# SCH_shield_test_2024-01-07.net
KiCad netlist of a schematic drawn in EasyEDA
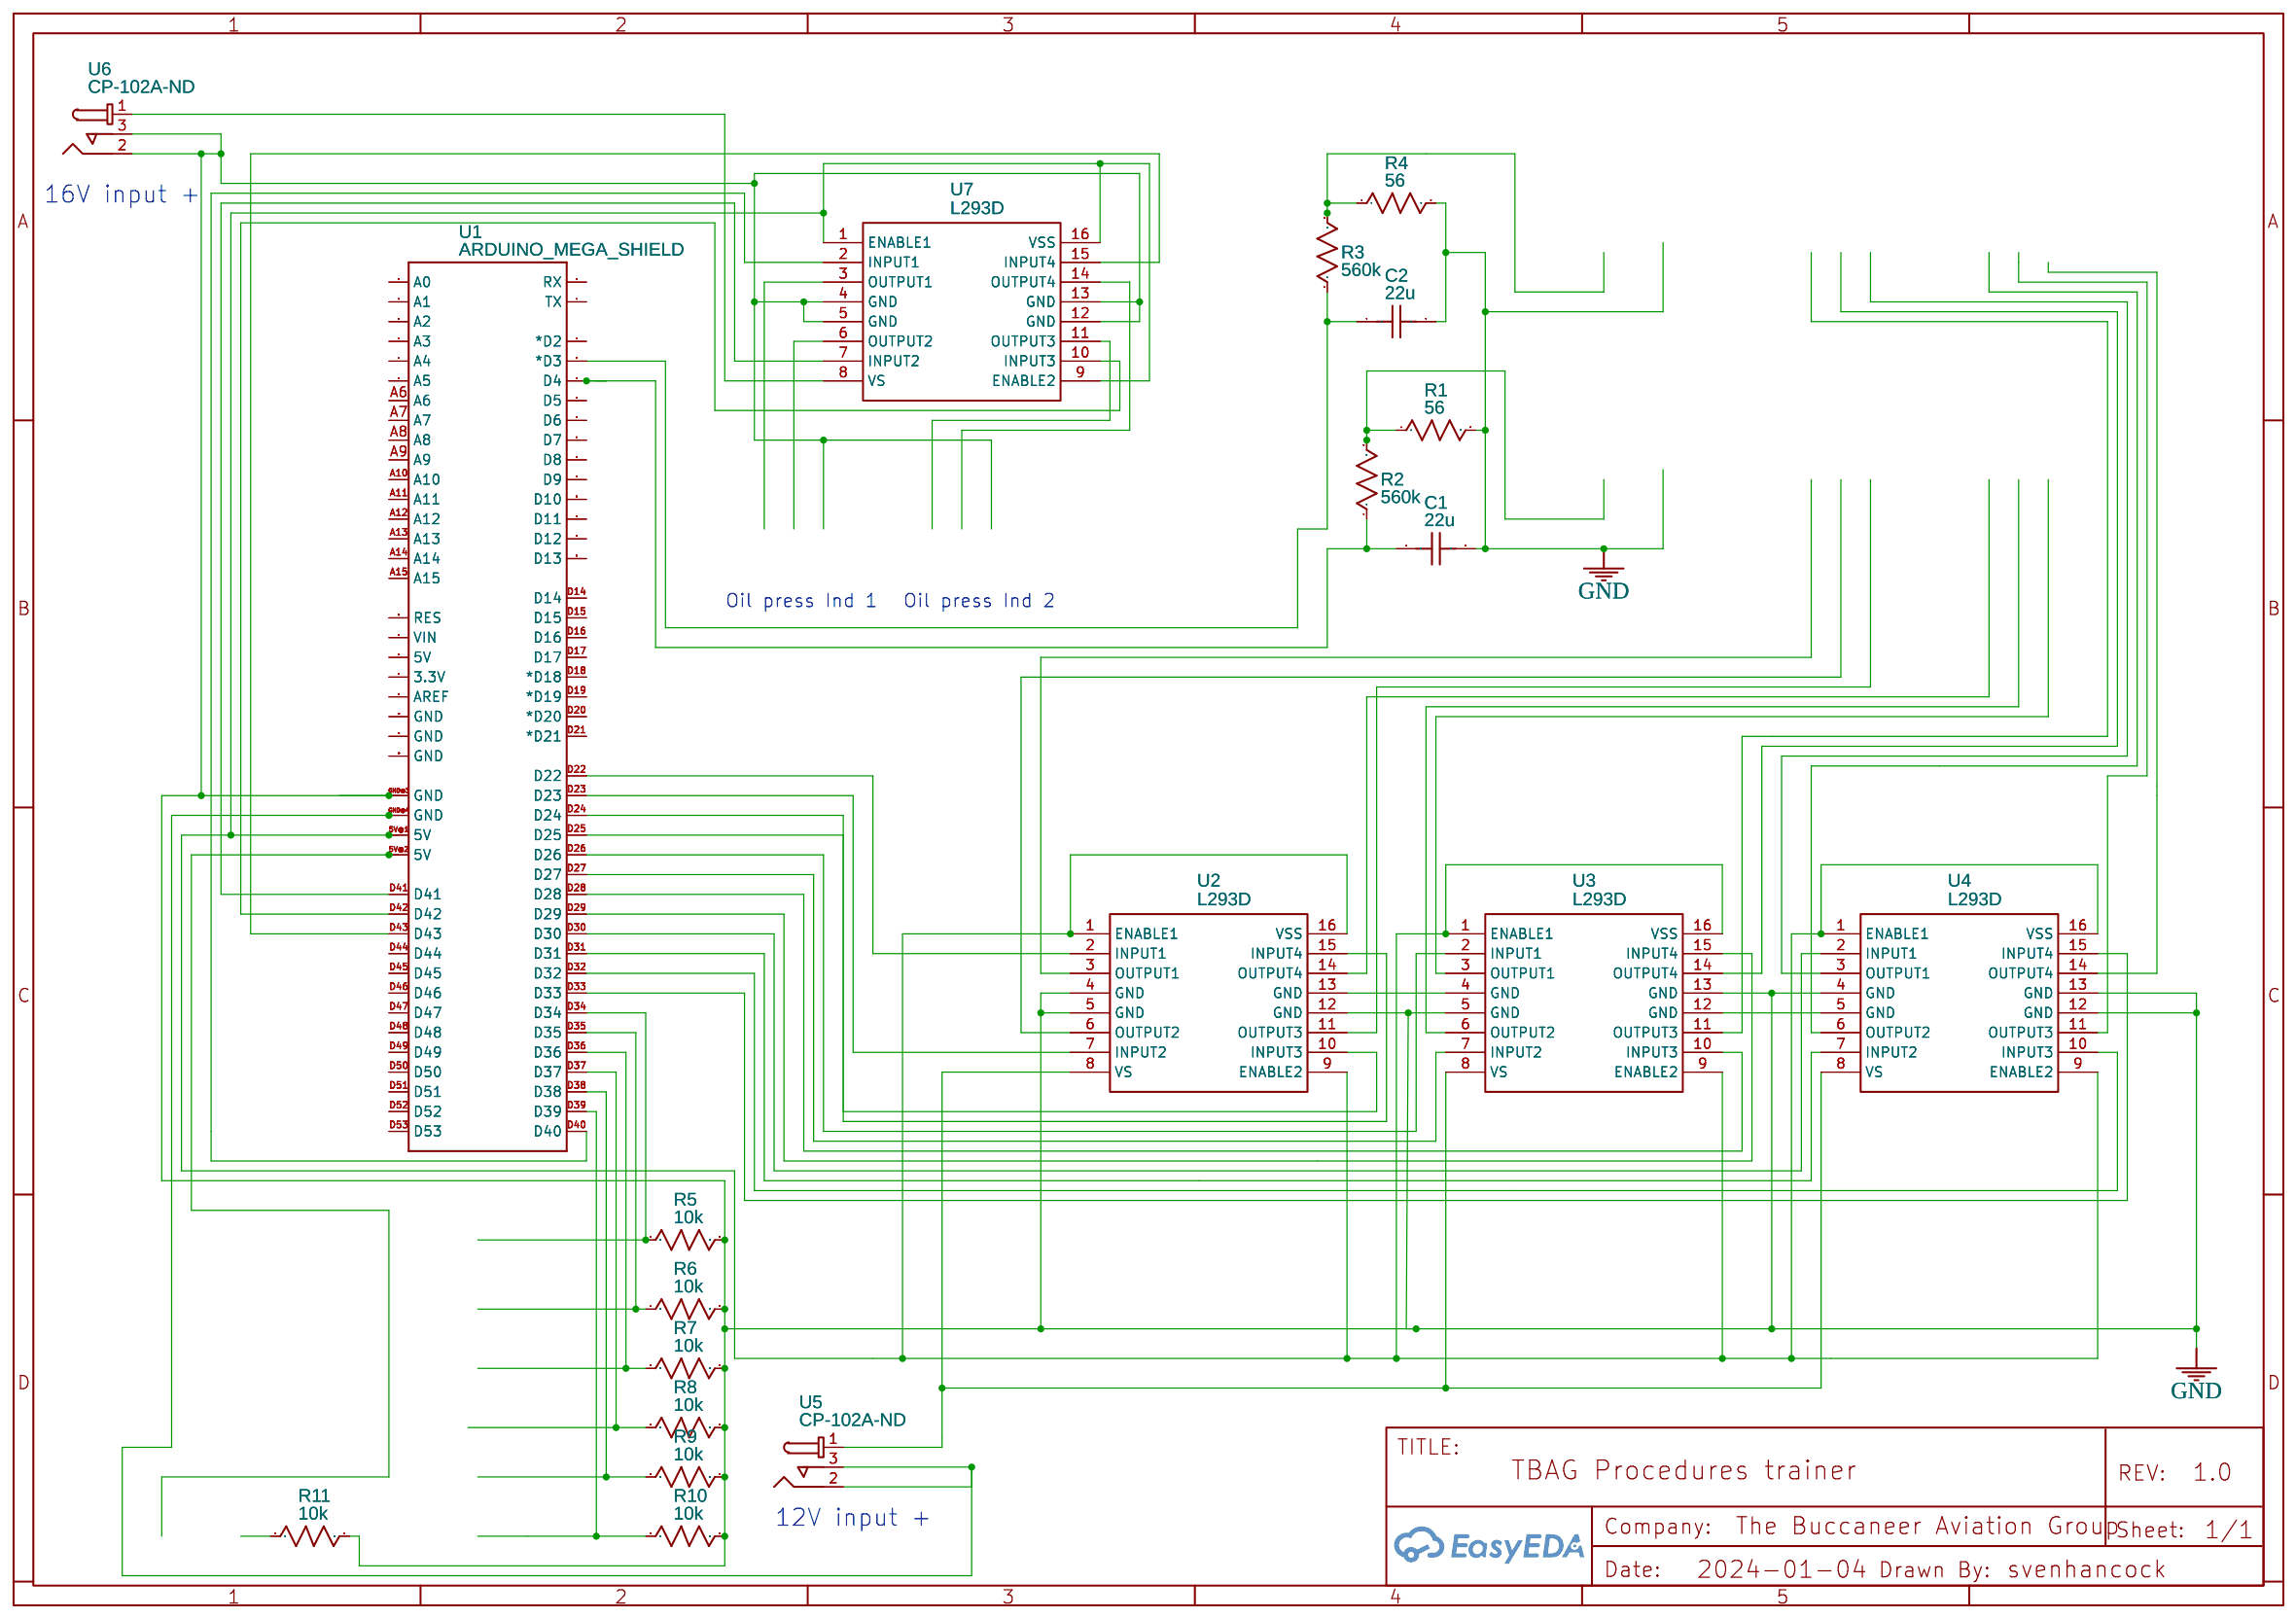
[diagram p0: schematic sheet]

(export (version "E")
  (design (tool "Eeschema 10.0.6"))
  (components
    (comp (ref "C1") (value "22u") (libsource (lib "") (part "C_0603_US")))
    (comp (ref "C2") (value "22u") (libsource (lib "") (part "C_0603_US")))
    (comp (ref "R1") (value "56") (libsource (lib "") (part "R_0603_US")))
    (comp (ref "R2") (value "560k") (libsource (lib "") (part "R_0603_US_1")))
    (comp (ref "R3") (value "560k") (libsource (lib "") (part "R_0603_US_1")))
    (comp (ref "R4") (value "56") (libsource (lib "") (part "R_0603_US")))
    (comp (ref "R5") (value "10k") (libsource (lib "") (part "R_0603_US")))
    (comp (ref "R6") (value "10k") (libsource (lib "") (part "R_0603_US")))
    (comp (ref "R7") (value "10k") (libsource (lib "") (part "R_0603_US")))
    (comp (ref "R8") (value "10k") (libsource (lib "") (part "R_0603_US")))
    (comp (ref "R9") (value "10k") (libsource (lib "") (part "R_0603_US")))
    (comp (ref "R10") (value "10k") (libsource (lib "") (part "R_0603_US")))
    (comp (ref "R11") (value "10k") (libsource (lib "") (part "R_0603_US")))
    (comp (ref "U1") (value "ARDUINO_MEGA_SHIELD") (libsource (lib "") (part "ARDUINO_MEGA_SHIELD")))
    (comp (ref "U2")
      (value "L293D")
      (fields (field (name "Manufacturer") "ST(意法半导体)"))
      (libsource (lib "") (part "L293D"))
    )
    (comp (ref "U3")
      (value "L293D")
      (fields (field (name "Manufacturer") "ST(意法半导体)"))
      (libsource (lib "") (part "L293D"))
    )
    (comp (ref "U4")
      (value "L293D")
      (fields (field (name "Manufacturer") "ST(意法半导体)"))
      (libsource (lib "") (part "L293D"))
    )
    (comp (ref "U5") (value "CP-102A-ND") (libsource (lib "") (part "CP-102A-ND")))
    (comp (ref "U6") (value "CP-102A-ND") (libsource (lib "") (part "CP-102A-ND")))
    (comp (ref "U7")
      (value "L293D")
      (fields (field (name "Manufacturer") "ST(意法半导体)"))
      (libsource (lib "") (part "L293D"))
    )
  )
  (nets
    (net (code "1") (name "GND") (class "Default")
      (node (ref "C1") (pin "2") (pinfunction "2_2") (pintype "unspecified"))
      (node (ref "C2") (pin "2") (pinfunction "2_2") (pintype "unspecified"))
      (node (ref "R1") (pin "2") (pinfunction "2_2") (pintype "unspecified"))
      (node (ref "R10") (pin "2") (pinfunction "2_2") (pintype "unspecified"))
      (node (ref "R11") (pin "2") (pinfunction "2_2") (pintype "unspecified"))
      (node (ref "R4") (pin "2") (pinfunction "2_2") (pintype "unspecified"))
      (node (ref "R5") (pin "2") (pinfunction "2_2") (pintype "unspecified"))
      (node (ref "R6") (pin "2") (pinfunction "2_2") (pintype "unspecified"))
      (node (ref "R7") (pin "2") (pinfunction "2_2") (pintype "unspecified"))
      (node (ref "R8") (pin "2") (pinfunction "2_2") (pintype "unspecified"))
      (node (ref "R9") (pin "2") (pinfunction "2_2") (pintype "unspecified"))
      (node (ref "U1") (pin "GND@3") (pinfunction "GND_GND@3") (pintype "unspecified"))
      (node (ref "U2") (pin "12") (pinfunction "GND_12") (pintype "unspecified"))
      (node (ref "U2") (pin "4") (pinfunction "GND_4") (pintype "unspecified"))
      (node (ref "U2") (pin "5") (pinfunction "GND_5") (pintype "unspecified"))
      (node (ref "U3") (pin "13") (pinfunction "GND_13") (pintype "unspecified"))
      (node (ref "U3") (pin "5") (pinfunction "GND_5") (pintype "unspecified"))
      (node (ref "U4") (pin "12") (pinfunction "GND_12") (pintype "unspecified"))
      (node (ref "U4") (pin "13") (pinfunction "GND_13") (pintype "unspecified"))
      (node (ref "U4") (pin "4") (pinfunction "GND_4") (pintype "unspecified"))
      (node (ref "U6") (pin "2") (pintype "unspecified"))
      (node (ref "U6") (pin "3") (pintype "unspecified"))
      (node (ref "U7") (pin "12") (pinfunction "GND_12") (pintype "unspecified"))
      (node (ref "U7") (pin "13") (pinfunction "GND_13") (pintype "unspecified"))
      (node (ref "U7") (pin "4") (pinfunction "GND_4") (pintype "unspecified"))
      (node (ref "U7") (pin "5") (pinfunction "GND_5") (pintype "unspecified"))
    )
    (net (code "2") (name "Net-(C1-Pad1)") (class "Default")
      (node (ref "C1") (pin "1") (pinfunction "1_1") (pintype "unspecified"))
      (node (ref "R2") (pin "1") (pinfunction "1_1") (pintype "unspecified"))
      (node (ref "U1") (pin "D4") (pinfunction "D4_D4") (pintype "unspecified"))
    )
    (net (code "3") (name "Net-(R1-Pad1)") (class "Default")
      (node (ref "R1") (pin "1") (pinfunction "1_1") (pintype "unspecified"))
      (node (ref "R2") (pin "2") (pinfunction "2_2") (pintype "unspecified"))
    )
    (net (code "4") (name "Net-(R3-Pad2)") (class "Default")
      (node (ref "R3") (pin "2") (pinfunction "2_2") (pintype "unspecified"))
      (node (ref "R4") (pin "1") (pinfunction "1_1") (pintype "unspecified"))
    )
    (net (code "5") (name "Net-(R5-Pad1)") (class "Default")
      (node (ref "R5") (pin "1") (pinfunction "1_1") (pintype "unspecified"))
      (node (ref "U1") (pin "D34") (pinfunction "D34_D34") (pintype "unspecified"))
    )
    (net (code "6") (name "Net-(R6-Pad1)") (class "Default")
      (node (ref "R6") (pin "1") (pinfunction "1_1") (pintype "unspecified"))
      (node (ref "U1") (pin "D35") (pinfunction "D35_D35") (pintype "unspecified"))
    )
    (net (code "7") (name "Net-(R7-Pad1)") (class "Default")
      (node (ref "R7") (pin "1") (pinfunction "1_1") (pintype "unspecified"))
      (node (ref "U1") (pin "D36") (pinfunction "D36_D36") (pintype "unspecified"))
    )
    (net (code "8") (name "Net-(R8-Pad1)") (class "Default")
      (node (ref "R8") (pin "1") (pinfunction "1_1") (pintype "unspecified"))
      (node (ref "U1") (pin "D37") (pinfunction "D37_D37") (pintype "unspecified"))
    )
    (net (code "9") (name "Net-(R9-Pad1)") (class "Default")
      (node (ref "R9") (pin "1") (pinfunction "1_1") (pintype "unspecified"))
      (node (ref "U1") (pin "D38") (pinfunction "D38_D38") (pintype "unspecified"))
    )
    (net (code "10") (name "Net-(R10-Pad1)") (class "Default")
      (node (ref "R10") (pin "1") (pinfunction "1_1") (pintype "unspecified"))
      (node (ref "U1") (pin "D39") (pinfunction "D39_D39") (pintype "unspecified"))
    )
    (net (code "11") (name "Net-(U1-*D3)") (class "Default")
      (node (ref "C2") (pin "1") (pinfunction "1_1") (pintype "unspecified"))
      (node (ref "R3") (pin "1") (pinfunction "1_1") (pintype "unspecified"))
      (node (ref "U1") (pin "D3") (pinfunction "*D3_D3") (pintype "unspecified"))
    )
    (net (code "12") (name "Net-(U1-GND-PadGND@4)") (class "Default")
      (node (ref "U1") (pin "GND@4") (pinfunction "GND_GND@4") (pintype "unspecified"))
      (node (ref "U5") (pin "2") (pintype "unspecified"))
      (node (ref "U5") (pin "3") (pintype "unspecified"))
    )
    (net (code "13") (name "Net-(U2-ENABLE1)") (class "Default")
      (node (ref "U1") (pin "5V@1") (pinfunction "5V_5V@1") (pintype "unspecified"))
      (node (ref "U2") (pin "1") (pinfunction "ENABLE1_1") (pintype "unspecified"))
      (node (ref "U2") (pin "16") (pinfunction "VSS_16") (pintype "unspecified"))
      (node (ref "U2") (pin "9") (pinfunction "ENABLE2_9") (pintype "unspecified"))
      (node (ref "U3") (pin "1") (pinfunction "ENABLE1_1") (pintype "unspecified"))
      (node (ref "U3") (pin "16") (pinfunction "VSS_16") (pintype "unspecified"))
      (node (ref "U3") (pin "9") (pinfunction "ENABLE2_9") (pintype "unspecified"))
      (node (ref "U4") (pin "1") (pinfunction "ENABLE1_1") (pintype "unspecified"))
      (node (ref "U4") (pin "16") (pinfunction "VSS_16") (pintype "unspecified"))
      (node (ref "U4") (pin "9") (pinfunction "ENABLE2_9") (pintype "unspecified"))
      (node (ref "U7") (pin "1") (pinfunction "ENABLE1_1") (pintype "unspecified"))
      (node (ref "U7") (pin "16") (pinfunction "VSS_16") (pintype "unspecified"))
      (node (ref "U7") (pin "9") (pinfunction "ENABLE2_9") (pintype "unspecified"))
    )
    (net (code "14") (name "Net-(U2-GND-Pad13)") (class "Default")
      (node (ref "U2") (pin "13") (pinfunction "GND_13") (pintype "unspecified"))
      (node (ref "U3") (pin "4") (pinfunction "GND_4") (pintype "unspecified"))
    )
    (net (code "15") (name "Net-(U2-INPUT1)") (class "Default")
      (node (ref "U1") (pin "D22") (pinfunction "D22_D22") (pintype "unspecified"))
      (node (ref "U2") (pin "2") (pinfunction "INPUT1_2") (pintype "unspecified"))
    )
    (net (code "16") (name "Net-(U2-INPUT2)") (class "Default")
      (node (ref "U1") (pin "D23") (pinfunction "D23_D23") (pintype "unspecified"))
      (node (ref "U2") (pin "7") (pinfunction "INPUT2_7") (pintype "unspecified"))
    )
    (net (code "17") (name "Net-(U2-INPUT3)") (class "Default")
      (node (ref "U1") (pin "D24") (pinfunction "D24_D24") (pintype "unspecified"))
      (node (ref "U2") (pin "10") (pinfunction "INPUT3_10") (pintype "unspecified"))
    )
    (net (code "18") (name "Net-(U2-INPUT4)") (class "Default")
      (node (ref "U1") (pin "D25") (pinfunction "D25_D25") (pintype "unspecified"))
      (node (ref "U2") (pin "15") (pinfunction "INPUT4_15") (pintype "unspecified"))
    )
    (net (code "19") (name "Net-(U2-VS)") (class "Default")
      (node (ref "U2") (pin "8") (pinfunction "VS_8") (pintype "unspecified"))
      (node (ref "U3") (pin "8") (pinfunction "VS_8") (pintype "unspecified"))
      (node (ref "U4") (pin "8") (pinfunction "VS_8") (pintype "unspecified"))
      (node (ref "U5") (pin "1") (pintype "unspecified"))
    )
    (net (code "20") (name "Net-(U3-GND-Pad12)") (class "Default")
      (node (ref "U3") (pin "12") (pinfunction "GND_12") (pintype "unspecified"))
      (node (ref "U4") (pin "5") (pinfunction "GND_5") (pintype "unspecified"))
    )
    (net (code "21") (name "Net-(U3-INPUT1)") (class "Default")
      (node (ref "U1") (pin "D26") (pinfunction "D26_D26") (pintype "unspecified"))
      (node (ref "U3") (pin "2") (pinfunction "INPUT1_2") (pintype "unspecified"))
    )
    (net (code "22") (name "Net-(U3-INPUT2)") (class "Default")
      (node (ref "U1") (pin "D27") (pinfunction "D27_D27") (pintype "unspecified"))
      (node (ref "U3") (pin "7") (pinfunction "INPUT2_7") (pintype "unspecified"))
    )
    (net (code "23") (name "Net-(U3-INPUT3)") (class "Default")
      (node (ref "U1") (pin "D28") (pinfunction "D28_D28") (pintype "unspecified"))
      (node (ref "U3") (pin "10") (pinfunction "INPUT3_10") (pintype "unspecified"))
    )
    (net (code "24") (name "Net-(U3-INPUT4)") (class "Default")
      (node (ref "U1") (pin "D29") (pinfunction "D29_D29") (pintype "unspecified"))
      (node (ref "U3") (pin "15") (pinfunction "INPUT4_15") (pintype "unspecified"))
    )
    (net (code "25") (name "Net-(U4-INPUT1)") (class "Default")
      (node (ref "U1") (pin "D30") (pinfunction "D30_D30") (pintype "unspecified"))
      (node (ref "U4") (pin "2") (pinfunction "INPUT1_2") (pintype "unspecified"))
    )
    (net (code "26") (name "Net-(U4-INPUT2)") (class "Default")
      (node (ref "U1") (pin "D31") (pinfunction "D31_D31") (pintype "unspecified"))
      (node (ref "U4") (pin "7") (pinfunction "INPUT2_7") (pintype "unspecified"))
    )
    (net (code "27") (name "Net-(U4-INPUT3)") (class "Default")
      (node (ref "U1") (pin "D32") (pinfunction "D32_D32") (pintype "unspecified"))
      (node (ref "U4") (pin "10") (pinfunction "INPUT3_10") (pintype "unspecified"))
    )
    (net (code "28") (name "Net-(U4-INPUT4)") (class "Default")
      (node (ref "U1") (pin "D33") (pinfunction "D33_D33") (pintype "unspecified"))
      (node (ref "U4") (pin "15") (pinfunction "INPUT4_15") (pintype "unspecified"))
    )
    (net (code "29") (name "Net-(U7-INPUT1)") (class "Default")
      (node (ref "U1") (pin "D40") (pinfunction "D40_D40") (pintype "unspecified"))
      (node (ref "U7") (pin "2") (pinfunction "INPUT1_2") (pintype "unspecified"))
    )
    (net (code "30") (name "Net-(U7-INPUT2)") (class "Default")
      (node (ref "U1") (pin "D41") (pinfunction "D41_D41") (pintype "unspecified"))
      (node (ref "U7") (pin "7") (pinfunction "INPUT2_7") (pintype "unspecified"))
    )
    (net (code "31") (name "Net-(U7-INPUT3)") (class "Default")
      (node (ref "U1") (pin "D42") (pinfunction "D42_D42") (pintype "unspecified"))
      (node (ref "U7") (pin "10") (pinfunction "INPUT3_10") (pintype "unspecified"))
    )
    (net (code "32") (name "Net-(U7-INPUT4)") (class "Default")
      (node (ref "U1") (pin "D43") (pinfunction "D43_D43") (pintype "unspecified"))
      (node (ref "U7") (pin "15") (pinfunction "INPUT4_15") (pintype "unspecified"))
    )
    (net (code "33") (name "Net-(U7-VS)") (class "Default")
      (node (ref "U6") (pin "1") (pintype "unspecified"))
      (node (ref "U7") (pin "8") (pinfunction "VS_8") (pintype "unspecified"))
    )
    (net (code "34") (name "unconnected-(R11-Pad1)") (class "Default")
      (node (ref "R11") (pin "1") (pinfunction "1_1") (pintype "unspecified"))
    )
    (net (code "35") (name "unconnected-(U1-*D2-PadD2)") (class "Default")
      (node (ref "U1") (pin "D2") (pinfunction "*D2_D2") (pintype "unspecified"))
    )
    (net (code "36") (name "unconnected-(U1-*D18-PadD18)") (class "Default")
      (node (ref "U1") (pin "D18") (pinfunction "*D18_D18") (pintype "unspecified"))
    )
    (net (code "37") (name "unconnected-(U1-*D19-PadD19)") (class "Default")
      (node (ref "U1") (pin "D19") (pinfunction "*D19_D19") (pintype "unspecified"))
    )
    (net (code "38") (name "unconnected-(U1-*D20-PadD20)") (class "Default")
      (node (ref "U1") (pin "D20") (pinfunction "*D20_D20") (pintype "unspecified"))
    )
    (net (code "39") (name "unconnected-(U1-*D21-PadD21)") (class "Default")
      (node (ref "U1") (pin "D21") (pinfunction "*D21_D21") (pintype "unspecified"))
    )
    (net (code "40") (name "unconnected-(U1-5V-Pad5V@0)") (class "Default")
      (node (ref "U1") (pin "5V@0") (pinfunction "5V_5V@0") (pintype "passive"))
    )
    (net (code "41") (name "unconnected-(U1-5V-Pad5V@2)") (class "Default")
      (node (ref "U1") (pin "5V@2") (pinfunction "5V_5V@2") (pintype "unspecified"))
    )
    (net (code "42") (name "unconnected-(U1-GND-PadGND@0)") (class "Default")
      (node (ref "U1") (pin "GND@0") (pinfunction "GND_GND@0") (pintype "unspecified"))
    )
    (net (code "43") (name "unconnected-(U1-GND-PadGND@1)") (class "Default")
      (node (ref "U1") (pin "GND@1") (pinfunction "GND_GND@1") (pintype "unspecified"))
    )
    (net (code "44") (name "unconnected-(U1-GND-PadGND@2)") (class "Default")
      (node (ref "U1") (pin "GND@2") (pinfunction "GND_GND@2") (pintype "unspecified"))
    )
    (net (code "45") (name "unconnected-(U1-Pad3.3V)") (class "Default")
      (node (ref "U1") (pin "3.3V") (pinfunction "3.3V_3.3V") (pintype "unspecified"))
    )
    (net (code "46") (name "unconnected-(U1-PadA0)") (class "Default")
      (node (ref "U1") (pin "A0") (pinfunction "A0_A0") (pintype "unspecified"))
    )
    (net (code "47") (name "unconnected-(U1-PadA1)") (class "Default")
      (node (ref "U1") (pin "A1") (pinfunction "A1_A1") (pintype "unspecified"))
    )
    (net (code "48") (name "unconnected-(U1-PadA2)") (class "Default")
      (node (ref "U1") (pin "A2") (pinfunction "A2_A2") (pintype "unspecified"))
    )
    (net (code "49") (name "unconnected-(U1-PadA3)") (class "Default")
      (node (ref "U1") (pin "A3") (pinfunction "A3_A3") (pintype "unspecified"))
    )
    (net (code "50") (name "unconnected-(U1-PadA4)") (class "Default")
      (node (ref "U1") (pin "A4") (pinfunction "A4_A4") (pintype "unspecified"))
    )
    (net (code "51") (name "unconnected-(U1-PadA5)") (class "Default")
      (node (ref "U1") (pin "A5") (pinfunction "A5_A5") (pintype "unspecified"))
    )
    (net (code "52") (name "unconnected-(U1-PadA6)") (class "Default")
      (node (ref "U1") (pin "A6") (pinfunction "A6_A6") (pintype "unspecified"))
    )
    (net (code "53") (name "unconnected-(U1-PadA7)") (class "Default")
      (node (ref "U1") (pin "A7") (pinfunction "A7_A7") (pintype "unspecified"))
    )
    (net (code "54") (name "unconnected-(U1-PadA8)") (class "Default")
      (node (ref "U1") (pin "A8") (pinfunction "A8_A8") (pintype "unspecified"))
    )
    (net (code "55") (name "unconnected-(U1-PadA9)") (class "Default")
      (node (ref "U1") (pin "A9") (pinfunction "A9_A9") (pintype "unspecified"))
    )
    (net (code "56") (name "unconnected-(U1-PadA10)") (class "Default")
      (node (ref "U1") (pin "A10") (pinfunction "A10_A10") (pintype "unspecified"))
    )
    (net (code "57") (name "unconnected-(U1-PadA11)") (class "Default")
      (node (ref "U1") (pin "A11") (pinfunction "A11_A11") (pintype "unspecified"))
    )
    (net (code "58") (name "unconnected-(U1-PadA12)") (class "Default")
      (node (ref "U1") (pin "A12") (pinfunction "A12_A12") (pintype "unspecified"))
    )
    (net (code "59") (name "unconnected-(U1-PadA13)") (class "Default")
      (node (ref "U1") (pin "A13") (pinfunction "A13_A13") (pintype "unspecified"))
    )
    (net (code "60") (name "unconnected-(U1-PadA14)") (class "Default")
      (node (ref "U1") (pin "A14") (pinfunction "A14_A14") (pintype "unspecified"))
    )
    (net (code "61") (name "unconnected-(U1-PadA15)") (class "Default")
      (node (ref "U1") (pin "A15") (pinfunction "A15_A15") (pintype "unspecified"))
    )
    (net (code "62") (name "unconnected-(U1-PadAREF)") (class "Default")
      (node (ref "U1") (pin "AREF") (pinfunction "AREF_AREF") (pintype "unspecified"))
    )
    (net (code "63") (name "unconnected-(U1-PadD5)") (class "Default")
      (node (ref "U1") (pin "D5") (pinfunction "D5_D5") (pintype "unspecified"))
    )
    (net (code "64") (name "unconnected-(U1-PadD6)") (class "Default")
      (node (ref "U1") (pin "D6") (pinfunction "D6_D6") (pintype "unspecified"))
    )
    (net (code "65") (name "unconnected-(U1-PadD7)") (class "Default")
      (node (ref "U1") (pin "D7") (pinfunction "D7_D7") (pintype "unspecified"))
    )
    (net (code "66") (name "unconnected-(U1-PadD8)") (class "Default")
      (node (ref "U1") (pin "D8") (pinfunction "D8_D8") (pintype "unspecified"))
    )
    (net (code "67") (name "unconnected-(U1-PadD9)") (class "Default")
      (node (ref "U1") (pin "D9") (pinfunction "D9_D9") (pintype "unspecified"))
    )
    (net (code "68") (name "unconnected-(U1-PadD10)") (class "Default")
      (node (ref "U1") (pin "D10") (pinfunction "D10_D10") (pintype "unspecified"))
    )
    (net (code "69") (name "unconnected-(U1-PadD11)") (class "Default")
      (node (ref "U1") (pin "D11") (pinfunction "D11_D11") (pintype "unspecified"))
    )
    (net (code "70") (name "unconnected-(U1-PadD12)") (class "Default")
      (node (ref "U1") (pin "D12") (pinfunction "D12_D12") (pintype "unspecified"))
    )
    (net (code "71") (name "unconnected-(U1-PadD13)") (class "Default")
      (node (ref "U1") (pin "D13") (pinfunction "D13_D13") (pintype "unspecified"))
    )
    (net (code "72") (name "unconnected-(U1-PadD14)") (class "Default")
      (node (ref "U1") (pin "D14") (pinfunction "D14_D14") (pintype "unspecified"))
    )
    (net (code "73") (name "unconnected-(U1-PadD15)") (class "Default")
      (node (ref "U1") (pin "D15") (pinfunction "D15_D15") (pintype "unspecified"))
    )
    (net (code "74") (name "unconnected-(U1-PadD16)") (class "Default")
      (node (ref "U1") (pin "D16") (pinfunction "D16_D16") (pintype "unspecified"))
    )
    (net (code "75") (name "unconnected-(U1-PadD17)") (class "Default")
      (node (ref "U1") (pin "D17") (pinfunction "D17_D17") (pintype "unspecified"))
    )
    (net (code "76") (name "unconnected-(U1-PadD44)") (class "Default")
      (node (ref "U1") (pin "D44") (pinfunction "D44_D44") (pintype "unspecified"))
    )
    (net (code "77") (name "unconnected-(U1-PadD45)") (class "Default")
      (node (ref "U1") (pin "D45") (pinfunction "D45_D45") (pintype "unspecified"))
    )
    (net (code "78") (name "unconnected-(U1-PadD46)") (class "Default")
      (node (ref "U1") (pin "D46") (pinfunction "D46_D46") (pintype "unspecified"))
    )
    (net (code "79") (name "unconnected-(U1-PadD47)") (class "Default")
      (node (ref "U1") (pin "D47") (pinfunction "D47_D47") (pintype "unspecified"))
    )
    (net (code "80") (name "unconnected-(U1-PadD48)") (class "Default")
      (node (ref "U1") (pin "D48") (pinfunction "D48_D48") (pintype "unspecified"))
    )
    (net (code "81") (name "unconnected-(U1-PadD49)") (class "Default")
      (node (ref "U1") (pin "D49") (pinfunction "D49_D49") (pintype "unspecified"))
    )
    (net (code "82") (name "unconnected-(U1-PadD50)") (class "Default")
      (node (ref "U1") (pin "D50") (pinfunction "D50_D50") (pintype "unspecified"))
    )
    (net (code "83") (name "unconnected-(U1-PadD51)") (class "Default")
      (node (ref "U1") (pin "D51") (pinfunction "D51_D51") (pintype "unspecified"))
    )
    (net (code "84") (name "unconnected-(U1-PadD52)") (class "Default")
      (node (ref "U1") (pin "D52") (pinfunction "D52_D52") (pintype "unspecified"))
    )
    (net (code "85") (name "unconnected-(U1-PadD53)") (class "Default")
      (node (ref "U1") (pin "D53") (pinfunction "D53_D53") (pintype "unspecified"))
    )
    (net (code "86") (name "unconnected-(U1-PadRES)") (class "Default")
      (node (ref "U1") (pin "RES") (pinfunction "RES_RES") (pintype "unspecified"))
    )
    (net (code "87") (name "unconnected-(U1-PadRX)") (class "Default")
      (node (ref "U1") (pin "RX") (pinfunction "RX_RX") (pintype "unspecified"))
    )
    (net (code "88") (name "unconnected-(U1-PadTX)") (class "Default")
      (node (ref "U1") (pin "TX") (pinfunction "TX_TX") (pintype "unspecified"))
    )
    (net (code "89") (name "unconnected-(U1-PadVIN)") (class "Default")
      (node (ref "U1") (pin "VIN") (pinfunction "VIN_VIN") (pintype "unspecified"))
    )
    (net (code "90") (name "unconnected-(U2-OUTPUT1-Pad3)") (class "Default")
      (node (ref "U2") (pin "3") (pinfunction "OUTPUT1_3") (pintype "unspecified"))
    )
    (net (code "91") (name "unconnected-(U2-OUTPUT2-Pad6)") (class "Default")
      (node (ref "U2") (pin "6") (pinfunction "OUTPUT2_6") (pintype "unspecified"))
    )
    (net (code "92") (name "unconnected-(U2-OUTPUT3-Pad11)") (class "Default")
      (node (ref "U2") (pin "11") (pinfunction "OUTPUT3_11") (pintype "unspecified"))
    )
    (net (code "93") (name "unconnected-(U2-OUTPUT4-Pad14)") (class "Default")
      (node (ref "U2") (pin "14") (pinfunction "OUTPUT4_14") (pintype "unspecified"))
    )
    (net (code "94") (name "unconnected-(U3-OUTPUT1-Pad3)") (class "Default")
      (node (ref "U3") (pin "3") (pinfunction "OUTPUT1_3") (pintype "unspecified"))
    )
    (net (code "95") (name "unconnected-(U3-OUTPUT2-Pad6)") (class "Default")
      (node (ref "U3") (pin "6") (pinfunction "OUTPUT2_6") (pintype "unspecified"))
    )
    (net (code "96") (name "unconnected-(U3-OUTPUT3-Pad11)") (class "Default")
      (node (ref "U3") (pin "11") (pinfunction "OUTPUT3_11") (pintype "unspecified"))
    )
    (net (code "97") (name "unconnected-(U3-OUTPUT4-Pad14)") (class "Default")
      (node (ref "U3") (pin "14") (pinfunction "OUTPUT4_14") (pintype "unspecified"))
    )
    (net (code "98") (name "unconnected-(U4-OUTPUT1-Pad3)") (class "Default")
      (node (ref "U4") (pin "3") (pinfunction "OUTPUT1_3") (pintype "unspecified"))
    )
    (net (code "99") (name "unconnected-(U4-OUTPUT2-Pad6)") (class "Default")
      (node (ref "U4") (pin "6") (pinfunction "OUTPUT2_6") (pintype "unspecified"))
    )
    (net (code "100") (name "unconnected-(U4-OUTPUT3-Pad11)") (class "Default")
      (node (ref "U4") (pin "11") (pinfunction "OUTPUT3_11") (pintype "unspecified"))
    )
    (net (code "101") (name "unconnected-(U4-OUTPUT4-Pad14)") (class "Default")
      (node (ref "U4") (pin "14") (pinfunction "OUTPUT4_14") (pintype "unspecified"))
    )
    (net (code "102") (name "unconnected-(U7-OUTPUT1-Pad3)") (class "Default")
      (node (ref "U7") (pin "3") (pinfunction "OUTPUT1_3") (pintype "unspecified"))
    )
    (net (code "103") (name "unconnected-(U7-OUTPUT2-Pad6)") (class "Default")
      (node (ref "U7") (pin "6") (pinfunction "OUTPUT2_6") (pintype "unspecified"))
    )
    (net (code "104") (name "unconnected-(U7-OUTPUT3-Pad11)") (class "Default")
      (node (ref "U7") (pin "11") (pinfunction "OUTPUT3_11") (pintype "unspecified"))
    )
    (net (code "105") (name "unconnected-(U7-OUTPUT4-Pad14)") (class "Default")
      (node (ref "U7") (pin "14") (pinfunction "OUTPUT4_14") (pintype "unspecified"))
    )
  )
)
